# 14_PHY_FE_41-48.net
KiCad netlist of a schematic drawn in Altium Designer
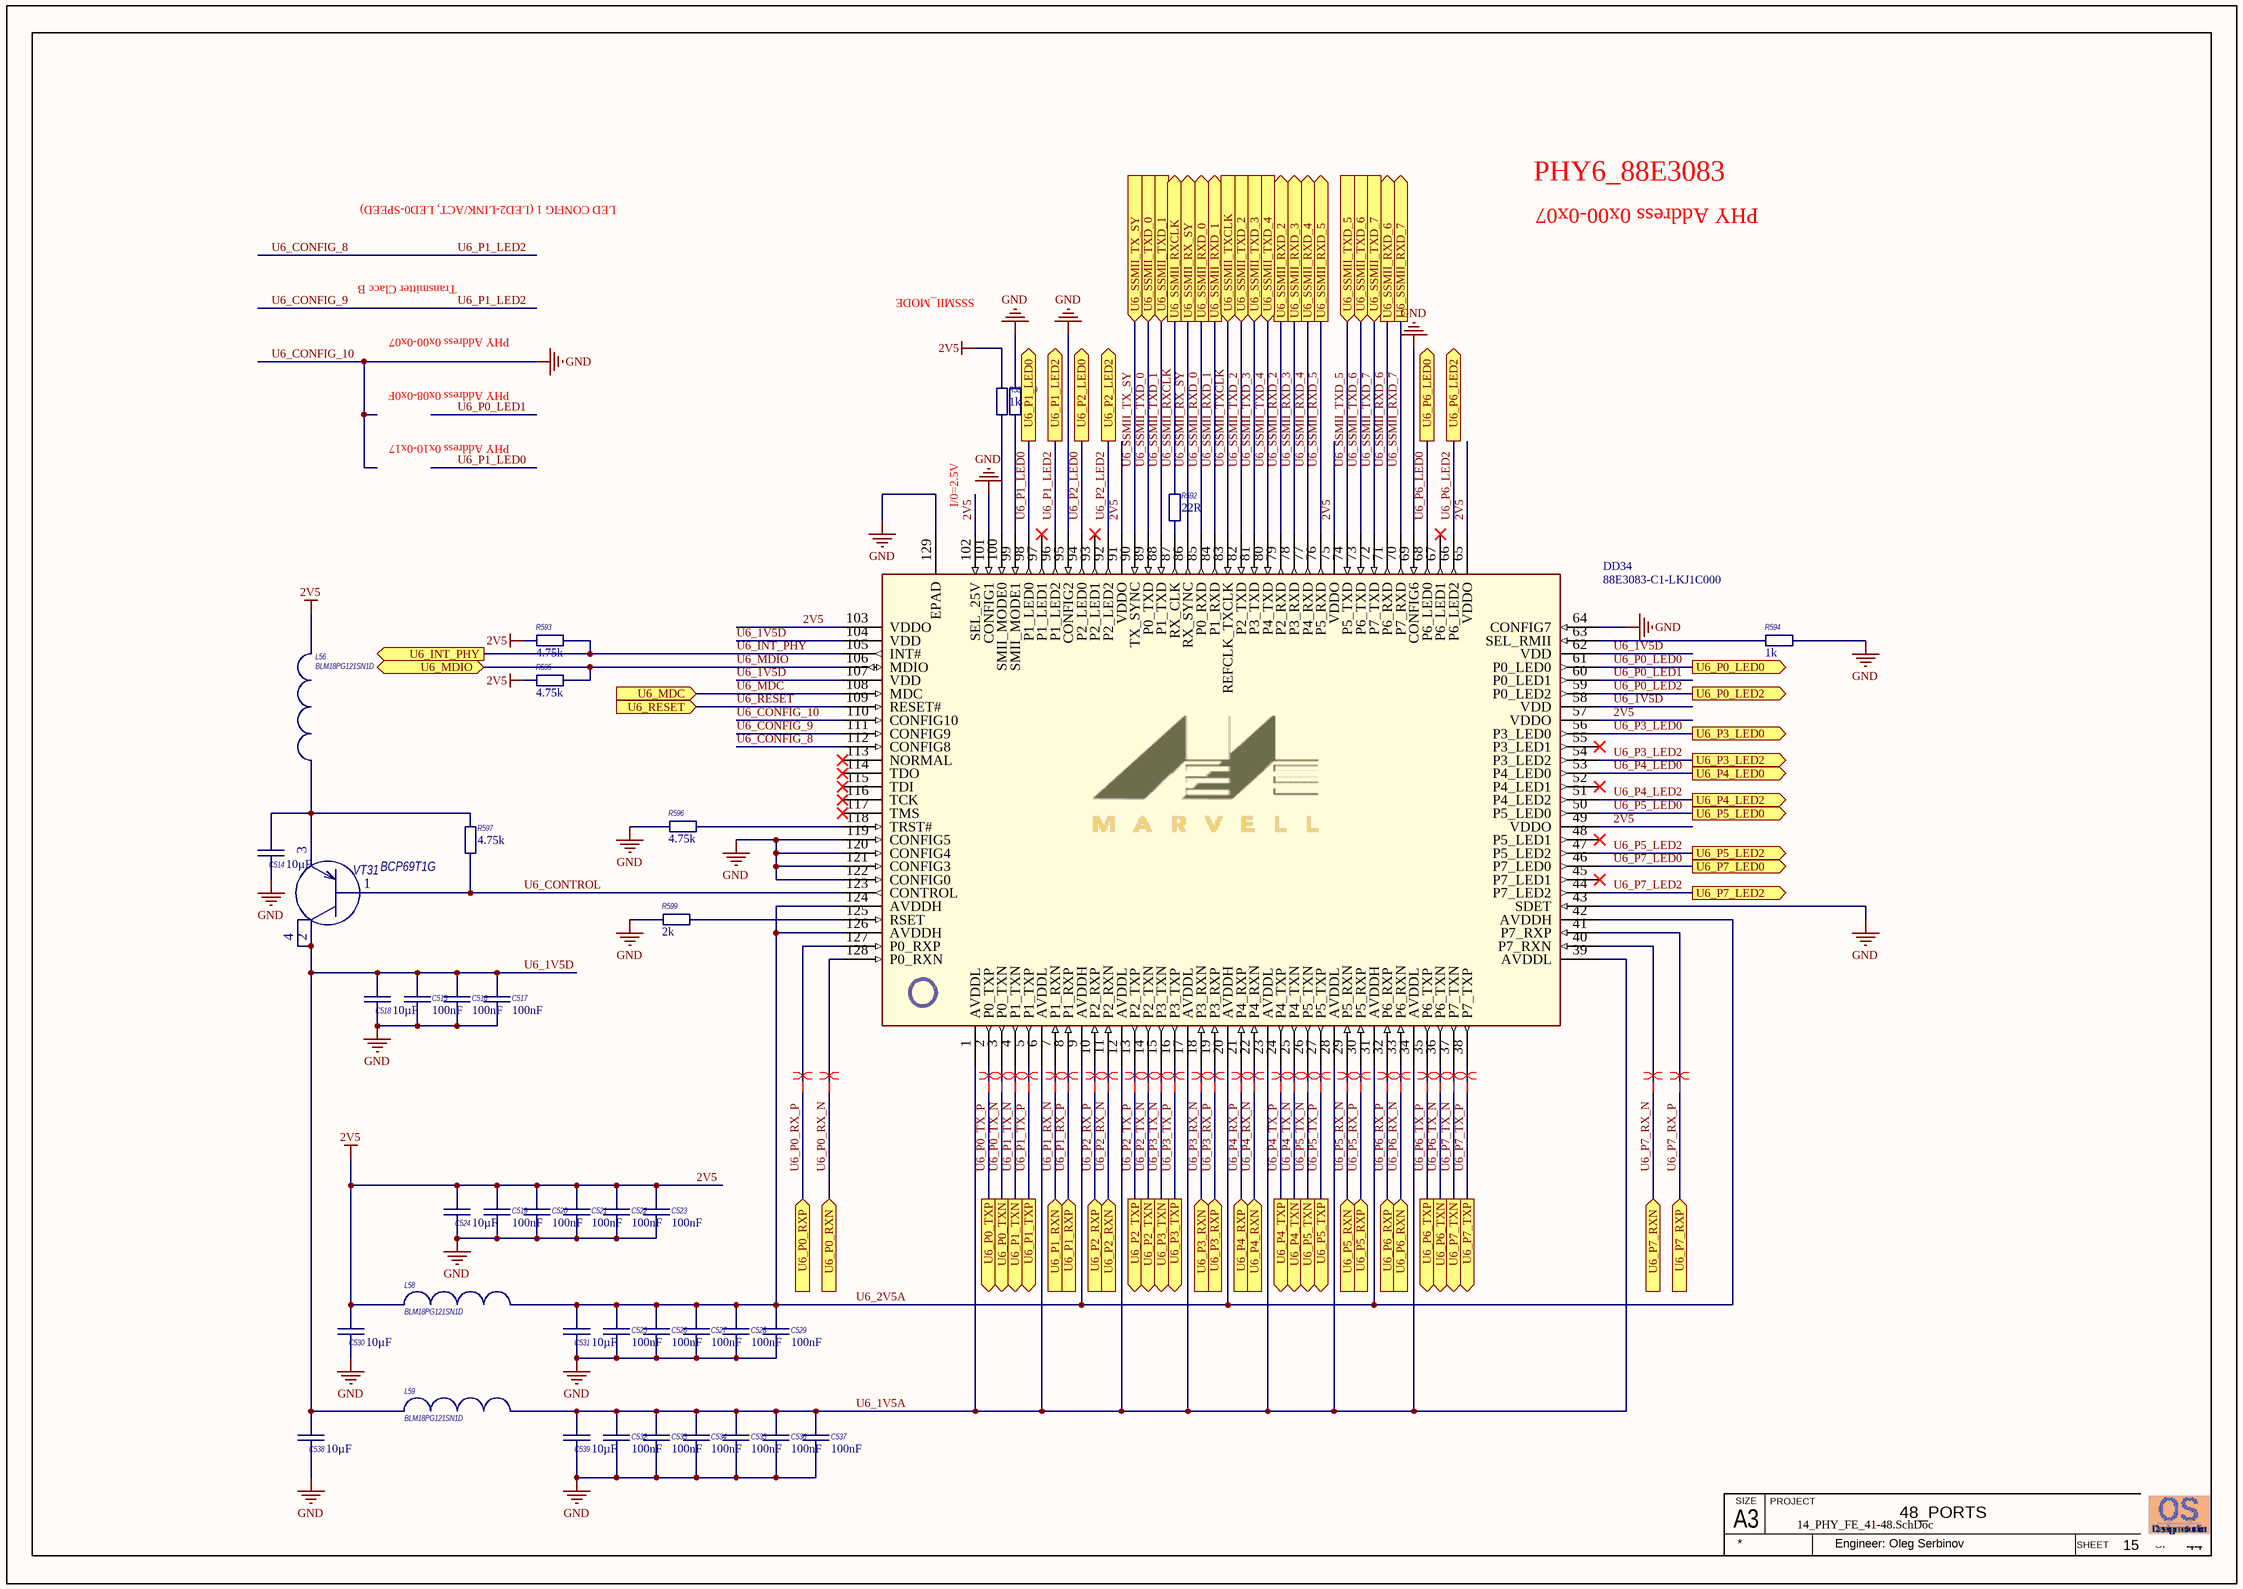
[diagram p0: 14_PHY_FE_41-48.SchDoc]

(export (version "E")
  (design (tool "Eeschema 10.0.6"))
  (components
    (comp (ref "C514")
      (value "GRM21BR61C106KE15")
      (footprint "CAPC2012[0805]")
      (description "C0805, 10uF 10%, 16V, X5R")
      (fields
        (field (name "MANUFACTURER") "Murata")
        (field (name "TOLERANCE") "±10%")
        (field (name "CAPACITANCE") "10µF")
      )
      (libsource (lib "CAPACITORS") (part "GRM21BR61C106KE15"))
    )
    (comp (ref "C515")
      (value "GRM155R71E104KE14D")
      (footprint "C0402_IPC High Density")
      (description "C0402, 100nF, 25V, X7R")
      (fields
        (field (name "MANUFACTURER") "Murata")
        (field (name "CAPACITANCE") "100nF")
        (field (name "CUSTOMER PART NUMBER") "Конденсатор, 100n, 0402, 25V, X7R, 10%")
      )
      (libsource (lib "CAPACITORS") (part "GRM155R71E104KE14D"))
    )
    (comp (ref "C516")
      (value "GRM155R71E104KE14D")
      (footprint "C0402_IPC High Density")
      (description "C0402, 100nF, 25V, X7R")
      (fields
        (field (name "MANUFACTURER") "Murata")
        (field (name "CAPACITANCE") "100nF")
        (field (name "CUSTOMER PART NUMBER") "Конденсатор, 100n, 0402, 25V, X7R, 10%")
      )
      (libsource (lib "CAPACITORS") (part "GRM155R71E104KE14D"))
    )
    (comp (ref "C517")
      (value "GRM155R71E104KE14D")
      (footprint "C0402_IPC High Density")
      (description "C0402, 100nF, 25V, X7R")
      (fields
        (field (name "MANUFACTURER") "Murata")
        (field (name "CAPACITANCE") "100nF")
        (field (name "CUSTOMER PART NUMBER") "Конденсатор, 100n, 0402, 25V, X7R, 10%")
      )
      (libsource (lib "CAPACITORS") (part "GRM155R71E104KE14D"))
    )
    (comp (ref "C518")
      (value "GRM21BR61C106KE15")
      (footprint "CAPC2012[0805]")
      (description "C0805, 10uF 10%, 16V, X5R")
      (fields
        (field (name "MANUFACTURER") "Murata")
        (field (name "TOLERANCE") "±10%")
        (field (name "CAPACITANCE") "10µF")
      )
      (libsource (lib "CAPACITORS") (part "GRM21BR61C106KE15"))
    )
    (comp (ref "C519")
      (value "GRM155R71E104KE14D")
      (footprint "C0402_IPC High Density")
      (description "C0402, 100nF, 25V, X7R")
      (fields
        (field (name "MANUFACTURER") "Murata")
        (field (name "CAPACITANCE") "100nF")
        (field (name "CUSTOMER PART NUMBER") "Конденсатор, 100n, 0402, 25V, X7R, 10%")
      )
      (libsource (lib "CAPACITORS") (part "GRM155R71E104KE14D"))
    )
    (comp (ref "C520")
      (value "GRM155R71E104KE14D")
      (footprint "C0402_IPC High Density")
      (description "C0402, 100nF, 25V, X7R")
      (fields
        (field (name "MANUFACTURER") "Murata")
        (field (name "CAPACITANCE") "100nF")
        (field (name "CUSTOMER PART NUMBER") "Конденсатор, 100n, 0402, 25V, X7R, 10%")
      )
      (libsource (lib "CAPACITORS") (part "GRM155R71E104KE14D"))
    )
    (comp (ref "C521")
      (value "GRM155R71E104KE14D")
      (footprint "C0402_IPC High Density")
      (description "C0402, 100nF, 25V, X7R")
      (fields
        (field (name "MANUFACTURER") "Murata")
        (field (name "CAPACITANCE") "100nF")
        (field (name "CUSTOMER PART NUMBER") "Конденсатор, 100n, 0402, 25V, X7R, 10%")
      )
      (libsource (lib "CAPACITORS") (part "GRM155R71E104KE14D"))
    )
    (comp (ref "C522")
      (value "GRM155R71E104KE14D")
      (footprint "C0402_IPC High Density")
      (description "C0402, 100nF, 25V, X7R")
      (fields
        (field (name "MANUFACTURER") "Murata")
        (field (name "CAPACITANCE") "100nF")
        (field (name "CUSTOMER PART NUMBER") "Конденсатор, 100n, 0402, 25V, X7R, 10%")
      )
      (libsource (lib "CAPACITORS") (part "GRM155R71E104KE14D"))
    )
    (comp (ref "C523")
      (value "GRM155R71E104KE14D")
      (footprint "C0402_IPC High Density")
      (description "C0402, 100nF, 25V, X7R")
      (fields
        (field (name "MANUFACTURER") "Murata")
        (field (name "CAPACITANCE") "100nF")
        (field (name "CUSTOMER PART NUMBER") "Конденсатор, 100n, 0402, 25V, X7R, 10%")
      )
      (libsource (lib "CAPACITORS") (part "GRM155R71E104KE14D"))
    )
    (comp (ref "C524")
      (value "GRM21BR61C106KE15")
      (footprint "CAPC2012[0805]")
      (description "C0805, 10uF 10%, 16V, X5R")
      (fields
        (field (name "MANUFACTURER") "Murata")
        (field (name "TOLERANCE") "±10%")
        (field (name "CAPACITANCE") "10µF")
      )
      (libsource (lib "CAPACITORS") (part "GRM21BR61C106KE15"))
    )
    (comp (ref "C525")
      (value "GRM155R71E104KE14D")
      (footprint "C0402_IPC High Density")
      (description "C0402, 100nF, 25V, X7R")
      (fields
        (field (name "MANUFACTURER") "Murata")
        (field (name "CAPACITANCE") "100nF")
        (field (name "CUSTOMER PART NUMBER") "Конденсатор, 100n, 0402, 25V, X7R, 10%")
      )
      (libsource (lib "CAPACITORS") (part "GRM155R71E104KE14D"))
    )
    (comp (ref "C526")
      (value "GRM155R71E104KE14D")
      (footprint "C0402_IPC High Density")
      (description "C0402, 100nF, 25V, X7R")
      (fields
        (field (name "MANUFACTURER") "Murata")
        (field (name "CAPACITANCE") "100nF")
        (field (name "CUSTOMER PART NUMBER") "Конденсатор, 100n, 0402, 25V, X7R, 10%")
      )
      (libsource (lib "CAPACITORS") (part "GRM155R71E104KE14D"))
    )
    (comp (ref "C527")
      (value "GRM155R71E104KE14D")
      (footprint "C0402_IPC High Density")
      (description "C0402, 100nF, 25V, X7R")
      (fields
        (field (name "MANUFACTURER") "Murata")
        (field (name "CAPACITANCE") "100nF")
        (field (name "CUSTOMER PART NUMBER") "Конденсатор, 100n, 0402, 25V, X7R, 10%")
      )
      (libsource (lib "CAPACITORS") (part "GRM155R71E104KE14D"))
    )
    (comp (ref "C528")
      (value "GRM155R71E104KE14D")
      (footprint "C0402_IPC High Density")
      (description "C0402, 100nF, 25V, X7R")
      (fields
        (field (name "MANUFACTURER") "Murata")
        (field (name "CAPACITANCE") "100nF")
        (field (name "CUSTOMER PART NUMBER") "Конденсатор, 100n, 0402, 25V, X7R, 10%")
      )
      (libsource (lib "CAPACITORS") (part "GRM155R71E104KE14D"))
    )
    (comp (ref "C529")
      (value "GRM155R71E104KE14D")
      (footprint "C0402_IPC High Density")
      (description "C0402, 100nF, 25V, X7R")
      (fields
        (field (name "MANUFACTURER") "Murata")
        (field (name "CAPACITANCE") "100nF")
        (field (name "CUSTOMER PART NUMBER") "Конденсатор, 100n, 0402, 25V, X7R, 10%")
      )
      (libsource (lib "CAPACITORS") (part "GRM155R71E104KE14D"))
    )
    (comp (ref "C530")
      (value "GRM21BR61C106KE15")
      (footprint "CAPC2012[0805]")
      (description "C0805, 10uF 10%, 16V, X5R")
      (fields
        (field (name "MANUFACTURER") "Murata")
        (field (name "TOLERANCE") "±10%")
        (field (name "CAPACITANCE") "10µF")
      )
      (libsource (lib "CAPACITORS") (part "GRM21BR61C106KE15"))
    )
    (comp (ref "C531")
      (value "GRM21BR61C106KE15")
      (footprint "CAPC2012[0805]")
      (description "C0805, 10uF 10%, 16V, X5R")
      (fields
        (field (name "MANUFACTURER") "Murata")
        (field (name "TOLERANCE") "±10%")
        (field (name "CAPACITANCE") "10µF")
      )
      (libsource (lib "CAPACITORS") (part "GRM21BR61C106KE15"))
    )
    (comp (ref "C532")
      (value "GRM155R71E104KE14D")
      (footprint "C0402_IPC High Density")
      (description "C0402, 100nF, 25V, X7R")
      (fields
        (field (name "MANUFACTURER") "Murata")
        (field (name "CAPACITANCE") "100nF")
        (field (name "CUSTOMER PART NUMBER") "Конденсатор, 100n, 0402, 25V, X7R, 10%")
      )
      (libsource (lib "CAPACITORS") (part "GRM155R71E104KE14D"))
    )
    (comp (ref "C533")
      (value "GRM155R71E104KE14D")
      (footprint "C0402_IPC High Density")
      (description "C0402, 100nF, 25V, X7R")
      (fields
        (field (name "MANUFACTURER") "Murata")
        (field (name "CAPACITANCE") "100nF")
        (field (name "CUSTOMER PART NUMBER") "Конденсатор, 100n, 0402, 25V, X7R, 10%")
      )
      (libsource (lib "CAPACITORS") (part "GRM155R71E104KE14D"))
    )
    (comp (ref "C534")
      (value "GRM155R71E104KE14D")
      (footprint "C0402_IPC High Density")
      (description "C0402, 100nF, 25V, X7R")
      (fields
        (field (name "MANUFACTURER") "Murata")
        (field (name "CAPACITANCE") "100nF")
        (field (name "CUSTOMER PART NUMBER") "Конденсатор, 100n, 0402, 25V, X7R, 10%")
      )
      (libsource (lib "CAPACITORS") (part "GRM155R71E104KE14D"))
    )
    (comp (ref "C535")
      (value "GRM155R71E104KE14D")
      (footprint "C0402_IPC High Density")
      (description "C0402, 100nF, 25V, X7R")
      (fields
        (field (name "MANUFACTURER") "Murata")
        (field (name "CAPACITANCE") "100nF")
        (field (name "CUSTOMER PART NUMBER") "Конденсатор, 100n, 0402, 25V, X7R, 10%")
      )
      (libsource (lib "CAPACITORS") (part "GRM155R71E104KE14D"))
    )
    (comp (ref "C536")
      (value "GRM155R71E104KE14D")
      (footprint "C0402_IPC High Density")
      (description "C0402, 100nF, 25V, X7R")
      (fields
        (field (name "MANUFACTURER") "Murata")
        (field (name "CAPACITANCE") "100nF")
        (field (name "CUSTOMER PART NUMBER") "Конденсатор, 100n, 0402, 25V, X7R, 10%")
      )
      (libsource (lib "CAPACITORS") (part "GRM155R71E104KE14D"))
    )
    (comp (ref "C537")
      (value "GRM155R71E104KE14D")
      (footprint "C0402_IPC High Density")
      (description "C0402, 100nF, 25V, X7R")
      (fields
        (field (name "MANUFACTURER") "Murata")
        (field (name "CAPACITANCE") "100nF")
        (field (name "CUSTOMER PART NUMBER") "Конденсатор, 100n, 0402, 25V, X7R, 10%")
      )
      (libsource (lib "CAPACITORS") (part "GRM155R71E104KE14D"))
    )
    (comp (ref "C538")
      (value "GRM21BR61C106KE15")
      (footprint "CAPC2012[0805]")
      (description "C0805, 10uF 10%, 16V, X5R")
      (fields
        (field (name "MANUFACTURER") "Murata")
        (field (name "TOLERANCE") "±10%")
        (field (name "CAPACITANCE") "10µF")
      )
      (libsource (lib "CAPACITORS") (part "GRM21BR61C106KE15"))
    )
    (comp (ref "C539")
      (value "GRM21BR61C106KE15")
      (footprint "CAPC2012[0805]")
      (description "C0805, 10uF 10%, 16V, X5R")
      (fields
        (field (name "MANUFACTURER") "Murata")
        (field (name "TOLERANCE") "±10%")
        (field (name "CAPACITANCE") "10µF")
      )
      (libsource (lib "CAPACITORS") (part "GRM21BR61C106KE15"))
    )
    (comp (ref "DD34")
      (value "88E3083-C1-LKJ1C000")
      (footprint "LQFP-128N")
      (description "IC 10/100BASE-T OCTAL PHY")
      (fields
        (field (name "CUSTOMER PART NUMBER") "Микросхема, 88E3083-C1-LKJ1C000, IC 10/100BASE-T OCTAL PHY, 128 LQFP")
        (field (name "MANUFACTURER") "Marvell Technology Group")
      )
      (libsource (lib "DIGITAL and ANALIG ICs") (part "88E3083-C1-LKJ1C000"))
    )
    (comp (ref "L56")
      (value "BLM18PG121SN1D")
      (footprint "INDC1608X95N")
      (description "FILTER BLM18 (0603, 2A)")
      (fields
        (field (name "MANUFACTURER") "Murata")
        (field (name "RPART NUMBER") "MPZ1608S121ATAH0 ; CIC10P121NC ; MPZ1608S121ATDH5 ; BLM18PG121SH1D ; 742792625")
      )
      (libsource (lib "INDUCTORS") (part "BLM18PG121SN1D"))
    )
    (comp (ref "L58")
      (value "BLM18PG121SN1D")
      (footprint "INDC1608X95N")
      (description "FILTER BLM18 (0603, 2A)")
      (fields
        (field (name "MANUFACTURER") "Murata")
        (field (name "RPART NUMBER") "MPZ1608S121ATAH0 ; CIC10P121NC ; MPZ1608S121ATDH5 ; BLM18PG121SH1D ; 742792625")
      )
      (libsource (lib "INDUCTORS") (part "BLM18PG121SN1D"))
    )
    (comp (ref "L59")
      (value "BLM18PG121SN1D")
      (footprint "INDC1608X95N")
      (description "FILTER BLM18 (0603, 2A)")
      (fields
        (field (name "MANUFACTURER") "Murata")
        (field (name "RPART NUMBER") "MPZ1608S121ATAH0 ; CIC10P121NC ; MPZ1608S121ATDH5 ; BLM18PG121SH1D ; 742792625")
      )
      (libsource (lib "INDUCTORS") (part "BLM18PG121SN1D"))
    )
    (comp (ref "R588")
      (value "ERJ-2RKF1001X")
      (footprint "R0402_IPC High Density")
      (description "R0402, 1k 1%")
      (fields
        (field (name "MANUFACTURER") "Panasonic")
        (field (name "TOLERANCE") "1 %")
        (field (name "RESISTANCE") "1k")
      )
      (libsource (lib "RESISTOR") (part "ERJ-2RKF1001X"))
    )
    (comp (ref "R589")
      (value "ERJ-2RKF1001X")
      (footprint "R0402_IPC High Density")
      (description "R0402, 1k 1%")
      (fields
        (field (name "MANUFACTURER") "Panasonic")
        (field (name "TOLERANCE") "1 %")
        (field (name "RESISTANCE") "1k")
      )
      (libsource (lib "RESISTOR") (part "ERJ-2RKF1001X"))
    )
    (comp (ref "R592")
      (value "ERJ-2RKF22R0X")
      (footprint "R0402_IPC High Density")
      (description "R0402, 22R 1%")
      (fields
        (field (name "MANUFACTURER") "Panasonic")
        (field (name "RESISTANCE") "22R")
        (field (name "CUSTOMER PART NUMBER") "Резистор, 22R, 0402, 1%")
      )
      (libsource (lib "RESISTOR") (part "ERJ-2RKF22R0X"))
    )
    (comp (ref "R593")
      (value "ERJ-2RKF4751X")
      (footprint "R0402_IPC High Density")
      (description "R0402, 4.75k 1%")
      (fields
        (field (name "TOLERANCE") "±1%")
        (field (name "MANUFACTURER") "Panasonic")
        (field (name "RESISTANCE (OHMS)") "4.75k")
      )
      (libsource (lib "RESISTOR") (part "ERJ-2RKF4751X"))
    )
    (comp (ref "R594")
      (value "ERJ-2RKF1001X")
      (footprint "R0402_IPC High Density")
      (description "R0402, 1k 1%")
      (fields
        (field (name "MANUFACTURER") "Panasonic")
        (field (name "TOLERANCE") "1 %")
        (field (name "RESISTANCE") "1k")
      )
      (libsource (lib "RESISTOR") (part "ERJ-2RKF1001X"))
    )
    (comp (ref "R595")
      (value "ERJ-2RKF4751X")
      (footprint "R0402_IPC High Density")
      (description "R0402, 4.75k 1%")
      (fields
        (field (name "TOLERANCE") "±1%")
        (field (name "MANUFACTURER") "Panasonic")
        (field (name "RESISTANCE (OHMS)") "4.75k")
      )
      (libsource (lib "RESISTOR") (part "ERJ-2RKF4751X"))
    )
    (comp (ref "R596")
      (value "ERJ-2RKF4751X")
      (footprint "R0402_IPC High Density")
      (description "R0402, 4.75k 1%")
      (fields
        (field (name "TOLERANCE") "±1%")
        (field (name "MANUFACTURER") "Panasonic")
        (field (name "RESISTANCE (OHMS)") "4.75k")
      )
      (libsource (lib "RESISTOR") (part "ERJ-2RKF4751X"))
    )
    (comp (ref "R597")
      (value "ERJ-2RKF4751X")
      (footprint "R0402_IPC High Density")
      (description "R0402, 4.75k 1%")
      (fields
        (field (name "TOLERANCE") "±1%")
        (field (name "MANUFACTURER") "Panasonic")
        (field (name "RESISTANCE (OHMS)") "4.75k")
      )
      (libsource (lib "RESISTOR") (part "ERJ-2RKF4751X"))
    )
    (comp (ref "R599")
      (value "ERJ-2RKF2001X")
      (footprint "R0402_IPC High Density")
      (description "R0402, 2k 1%")
      (fields
        (field (name "TOLERANCE") "±1%")
        (field (name "MANUFACTURER") "Panasonic")
        (field (name "RESISTANCE (OHMS)") "2k")
      )
      (libsource (lib "RESISTOR") (part "ERJ-2RKF2001X"))
    )
    (comp (ref "VT31")
      (value "BCP69T1G")
      (footprint "SOT223_N")
      (description "TRANSISTOR PNP -20V -1A SOT-223")
      (fields
        (field (name "MANUFACTURER") "ON Semiconductor")
        (field (name "MANUFACTURER PART NUMBER") "BCP69T1")
      )
      (libsource (lib "TRANSISTORS") (part "BCP69T1"))
    )
  )
  (nets
    (net (code "1") (name "/U6_1V5A") (class "Default")
      (node (ref "C532") (pin "2") (pintype "passive"))
      (node (ref "C533") (pin "2") (pintype "passive"))
      (node (ref "C534") (pin "2") (pintype "passive"))
      (node (ref "C535") (pin "2") (pintype "passive"))
      (node (ref "C536") (pin "2") (pintype "passive"))
      (node (ref "C537") (pin "2") (pintype "passive"))
      (node (ref "C539") (pin "2") (pintype "passive"))
      (node (ref "DD34") (pin "1") (pinfunction "AVDDL_1") (pintype "power_in"))
      (node (ref "DD34") (pin "12") (pinfunction "AVDDL_12") (pintype "power_in"))
      (node (ref "DD34") (pin "17") (pinfunction "AVDDL_17") (pintype "power_in"))
      (node (ref "DD34") (pin "23") (pinfunction "AVDDL_23") (pintype "power_in"))
      (node (ref "DD34") (pin "28") (pinfunction "AVDDL_28") (pintype "power_in"))
      (node (ref "DD34") (pin "34") (pinfunction "AVDDL_34") (pintype "power_in"))
      (node (ref "DD34") (pin "39") (pinfunction "AVDDL_39") (pintype "power_in"))
      (node (ref "DD34") (pin "6") (pinfunction "AVDDL_6") (pintype "power_in"))
      (node (ref "L59") (pin "2") (pinfunction "2_2") (pintype "passive"))
    )
    (net (code "2") (name "/U6_1V5D") (class "Default")
      (node (ref "C515") (pin "2") (pintype "passive"))
      (node (ref "C516") (pin "2") (pintype "passive"))
      (node (ref "C517") (pin "2") (pintype "passive"))
      (node (ref "C518") (pin "2") (pintype "passive"))
      (node (ref "C538") (pin "2") (pintype "passive"))
      (node (ref "DD34") (pin "104") (pinfunction "VDD_104") (pintype "power_in"))
      (node (ref "DD34") (pin "107") (pinfunction "VDD_107") (pintype "power_in"))
      (node (ref "DD34") (pin "58") (pinfunction "VDD_58") (pintype "power_in"))
      (node (ref "DD34") (pin "62") (pinfunction "VDD_62") (pintype "power_in"))
      (node (ref "L59") (pin "1") (pinfunction "1_1") (pintype "passive"))
      (node (ref "VT31") (pin "2") (pinfunction "K_2") (pintype "passive"))
      (node (ref "VT31") (pin "4") (pinfunction "K_4") (pintype "passive"))
    )
    (net (code "3") (name "/U6_2V5A") (class "Default")
      (node (ref "C525") (pin "2") (pintype "passive"))
      (node (ref "C526") (pin "2") (pintype "passive"))
      (node (ref "C527") (pin "2") (pintype "passive"))
      (node (ref "C528") (pin "2") (pintype "passive"))
      (node (ref "C529") (pin "2") (pintype "passive"))
      (node (ref "C531") (pin "2") (pintype "passive"))
      (node (ref "DD34") (pin "124") (pinfunction "AVDDH_124") (pintype "power_in"))
      (node (ref "DD34") (pin "126") (pinfunction "AVDDH_126") (pintype "power_in"))
      (node (ref "DD34") (pin "20") (pinfunction "AVDDH_20") (pintype "power_in"))
      (node (ref "DD34") (pin "31") (pinfunction "AVDDH_31") (pintype "power_in"))
      (node (ref "DD34") (pin "42") (pinfunction "AVDDH_42") (pintype "power_in"))
      (node (ref "DD34") (pin "9") (pinfunction "AVDDH_9") (pintype "power_in"))
      (node (ref "L58") (pin "2") (pinfunction "2_2") (pintype "passive"))
    )
    (net (code "4") (name "/U6_CONFIG_8") (class "Default")
      (node (ref "DD34") (pin "111") (pinfunction "CONFIG9_111") (pintype "input"))
      (node (ref "DD34") (pin "112") (pinfunction "CONFIG8_112") (pintype "input"))
      (node (ref "DD34") (pin "96") (pinfunction "P1_LED2_96") (pintype "output"))
    )
    (net (code "5") (name "/U6_CONTROL") (class "Default")
      (node (ref "DD34") (pin "123") (pinfunction "CONTROL_123") (pintype "output"))
      (node (ref "R597") (pin "1") (pintype "passive"))
      (node (ref "VT31") (pin "1") (pinfunction "B_1") (pintype "passive"))
    )
    (net (code "6") (name "/U6_INT_PHY") (class "Default")
      (node (ref "DD34") (pin "105") (pinfunction "INT#_105") (pintype "output"))
      (node (ref "R593") (pin "2") (pintype "passive"))
    )
    (net (code "7") (name "/U6_MDC") (class "Default")
      (node (ref "DD34") (pin "108") (pinfunction "MDC_108") (pintype "input"))
    )
    (net (code "8") (name "/U6_MDIO") (class "Default")
      (node (ref "DD34") (pin "106") (pinfunction "MDIO_106") (pintype "bidirectional"))
      (node (ref "R595") (pin "2") (pintype "passive"))
    )
    (net (code "9") (name "/U6_P0_LED0") (class "Default")
      (node (ref "DD34") (pin "61") (pinfunction "P0_LED0_61") (pintype "output"))
    )
    (net (code "10") (name "/U6_P0_LED1") (class "Default")
      (node (ref "DD34") (pin "60") (pinfunction "P0_LED1_60") (pintype "output"))
    )
    (net (code "11") (name "/U6_P0_LED2") (class "Default")
      (node (ref "DD34") (pin "59") (pinfunction "P0_LED2_59") (pintype "output"))
    )
    (net (code "12") (name "/U6_P0_RX_N") (class "Default")
      (node (ref "DD34") (pin "128") (pinfunction "P0_RXN_128") (pintype "input"))
    )
    (net (code "13") (name "/U6_P0_RX_P") (class "Default")
      (node (ref "DD34") (pin "127") (pinfunction "P0_RXP_127") (pintype "input"))
    )
    (net (code "14") (name "/U6_P0_TX_N") (class "Default")
      (node (ref "DD34") (pin "3") (pinfunction "P0_TXN_3") (pintype "output"))
    )
    (net (code "15") (name "/U6_P0_TX_P") (class "Default")
      (node (ref "DD34") (pin "2") (pinfunction "P0_TXP_2") (pintype "output"))
    )
    (net (code "16") (name "/U6_P1_LED0") (class "Default")
      (node (ref "DD34") (pin "98") (pinfunction "P1_LED0_98") (pintype "output"))
    )
    (net (code "17") (name "/U6_P1_RX_N") (class "Default")
      (node (ref "DD34") (pin "7") (pinfunction "P1_RXN_7") (pintype "input"))
    )
    (net (code "18") (name "/U6_P1_RX_P") (class "Default")
      (node (ref "DD34") (pin "8") (pinfunction "P1_RXP_8") (pintype "input"))
    )
    (net (code "19") (name "/U6_P1_TX_N") (class "Default")
      (node (ref "DD34") (pin "4") (pinfunction "P1_TXN_4") (pintype "output"))
    )
    (net (code "20") (name "/U6_P1_TX_P") (class "Default")
      (node (ref "DD34") (pin "5") (pinfunction "P1_TXP_5") (pintype "output"))
    )
    (net (code "21") (name "/U6_P2_LED0") (class "Default")
      (node (ref "DD34") (pin "94") (pinfunction "P2_LED0_94") (pintype "output"))
    )
    (net (code "22") (name "/U6_P2_LED2") (class "Default")
      (node (ref "DD34") (pin "92") (pinfunction "P2_LED2_92") (pintype "output"))
    )
    (net (code "23") (name "/U6_P2_RX_N") (class "Default")
      (node (ref "DD34") (pin "11") (pinfunction "P2_RXN_11") (pintype "input"))
    )
    (net (code "24") (name "/U6_P2_RX_P") (class "Default")
      (node (ref "DD34") (pin "10") (pinfunction "P2_RXP_10") (pintype "input"))
    )
    (net (code "25") (name "/U6_P2_TX_N") (class "Default")
      (node (ref "DD34") (pin "14") (pinfunction "P2_TXN_14") (pintype "output"))
    )
    (net (code "26") (name "/U6_P2_TX_P") (class "Default")
      (node (ref "DD34") (pin "13") (pinfunction "P2_TXP_13") (pintype "output"))
    )
    (net (code "27") (name "/U6_P3_LED0") (class "Default")
      (node (ref "DD34") (pin "56") (pinfunction "P3_LED0_56") (pintype "output"))
    )
    (net (code "28") (name "/U6_P3_LED2") (class "Default")
      (node (ref "DD34") (pin "54") (pinfunction "P3_LED2_54") (pintype "output"))
    )
    (net (code "29") (name "/U6_P3_RX_N") (class "Default")
      (node (ref "DD34") (pin "18") (pinfunction "P3_RXN_18") (pintype "input"))
    )
    (net (code "30") (name "/U6_P3_RX_P") (class "Default")
      (node (ref "DD34") (pin "19") (pinfunction "P3_RXP_19") (pintype "input"))
    )
    (net (code "31") (name "/U6_P3_TX_N") (class "Default")
      (node (ref "DD34") (pin "15") (pinfunction "P3_TXN_15") (pintype "output"))
    )
    (net (code "32") (name "/U6_P3_TX_P") (class "Default")
      (node (ref "DD34") (pin "16") (pinfunction "P3_TXP_16") (pintype "output"))
    )
    (net (code "33") (name "/U6_P4_LED0") (class "Default")
      (node (ref "DD34") (pin "53") (pinfunction "P4_LED0_53") (pintype "output"))
    )
    (net (code "34") (name "/U6_P4_LED2") (class "Default")
      (node (ref "DD34") (pin "51") (pinfunction "P4_LED2_51") (pintype "output"))
    )
    (net (code "35") (name "/U6_P4_RX_N") (class "Default")
      (node (ref "DD34") (pin "22") (pinfunction "P4_RXN_22") (pintype "input"))
    )
    (net (code "36") (name "/U6_P4_RX_P") (class "Default")
      (node (ref "DD34") (pin "21") (pinfunction "P4_RXP_21") (pintype "input"))
    )
    (net (code "37") (name "/U6_P4_TX_N") (class "Default")
      (node (ref "DD34") (pin "25") (pinfunction "P4_TXN_25") (pintype "output"))
    )
    (net (code "38") (name "/U6_P4_TX_P") (class "Default")
      (node (ref "DD34") (pin "24") (pinfunction "P4_TXP_24") (pintype "output"))
    )
    (net (code "39") (name "/U6_P5_LED0") (class "Default")
      (node (ref "DD34") (pin "50") (pinfunction "P5_LED0_50") (pintype "output"))
    )
    (net (code "40") (name "/U6_P5_LED2") (class "Default")
      (node (ref "DD34") (pin "47") (pinfunction "P5_LED2_47") (pintype "output"))
    )
    (net (code "41") (name "/U6_P5_RX_N") (class "Default")
      (node (ref "DD34") (pin "29") (pinfunction "P5_RXN_29") (pintype "input"))
    )
    (net (code "42") (name "/U6_P5_RX_P") (class "Default")
      (node (ref "DD34") (pin "30") (pinfunction "P5_RXP_30") (pintype "input"))
    )
    (net (code "43") (name "/U6_P5_TX_N") (class "Default")
      (node (ref "DD34") (pin "26") (pinfunction "P5_TXN_26") (pintype "output"))
    )
    (net (code "44") (name "/U6_P5_TX_P") (class "Default")
      (node (ref "DD34") (pin "27") (pinfunction "P5_TXP_27") (pintype "output"))
    )
    (net (code "45") (name "/U6_P6_LED0") (class "Default")
      (node (ref "DD34") (pin "68") (pinfunction "P6_LED0_68") (pintype "output"))
    )
    (net (code "46") (name "/U6_P6_LED2") (class "Default")
      (node (ref "DD34") (pin "66") (pinfunction "P6_LED2_66") (pintype "output"))
    )
    (net (code "47") (name "/U6_P6_RX_N") (class "Default")
      (node (ref "DD34") (pin "33") (pinfunction "P6_RXN_33") (pintype "input"))
    )
    (net (code "48") (name "/U6_P6_RX_P") (class "Default")
      (node (ref "DD34") (pin "32") (pinfunction "P6_RXP_32") (pintype "input"))
    )
    (net (code "49") (name "/U6_P6_TX_N") (class "Default")
      (node (ref "DD34") (pin "36") (pinfunction "P6_TXN_36") (pintype "output"))
    )
    (net (code "50") (name "/U6_P6_TX_P") (class "Default")
      (node (ref "DD34") (pin "35") (pinfunction "P6_TXP_35") (pintype "output"))
    )
    (net (code "51") (name "/U6_P7_LED0") (class "Default")
      (node (ref "DD34") (pin "46") (pinfunction "P7_LED0_46") (pintype "output"))
    )
    (net (code "52") (name "/U6_P7_LED2") (class "Default")
      (node (ref "DD34") (pin "44") (pinfunction "P7_LED2_44") (pintype "output"))
    )
    (net (code "53") (name "/U6_P7_RX_N") (class "Default")
      (node (ref "DD34") (pin "40") (pinfunction "P7_RXN_40") (pintype "input"))
    )
    (net (code "54") (name "/U6_P7_RX_P") (class "Default")
      (node (ref "DD34") (pin "41") (pinfunction "P7_RXP_41") (pintype "input"))
    )
    (net (code "55") (name "/U6_P7_TX_N") (class "Default")
      (node (ref "DD34") (pin "37") (pinfunction "P7_TXN_37") (pintype "output"))
    )
    (net (code "56") (name "/U6_P7_TX_P") (class "Default")
      (node (ref "DD34") (pin "38") (pinfunction "P7_TXP_38") (pintype "output"))
    )
    (net (code "57") (name "/U6_RESET") (class "Default")
      (node (ref "DD34") (pin "109") (pinfunction "RESET#_109") (pintype "input"))
    )
    (net (code "58") (name "/U6_SSMII_RXCLK") (class "Default")
      (node (ref "R592") (pin "2") (pintype "passive"))
    )
    (net (code "59") (name "/U6_SSMII_RXD_0") (class "Default")
      (node (ref "DD34") (pin "85") (pinfunction "P0_RXD_85") (pintype "output"))
    )
    (net (code "60") (name "/U6_SSMII_RXD_1") (class "Default")
      (node (ref "DD34") (pin "84") (pinfunction "P1_RXD_84") (pintype "output"))
    )
    (net (code "61") (name "/U6_SSMII_RXD_2") (class "Default")
      (node (ref "DD34") (pin "79") (pinfunction "P2_RXD_79") (pintype "output"))
    )
    (net (code "62") (name "/U6_SSMII_RXD_3") (class "Default")
      (node (ref "DD34") (pin "78") (pinfunction "P3_RXD_78") (pintype "output"))
    )
    (net (code "63") (name "/U6_SSMII_RXD_4") (class "Default")
      (node (ref "DD34") (pin "77") (pinfunction "P4_RXD_77") (pintype "output"))
    )
    (net (code "64") (name "/U6_SSMII_RXD_5") (class "Default")
      (node (ref "DD34") (pin "76") (pinfunction "P5_RXD_76") (pintype "output"))
    )
    (net (code "65") (name "/U6_SSMII_RXD_6") (class "Default")
      (node (ref "DD34") (pin "71") (pinfunction "P6_RXD_71") (pintype "output"))
    )
    (net (code "66") (name "/U6_SSMII_RXD_7") (class "Default")
      (node (ref "DD34") (pin "70") (pinfunction "P7_RXD_70") (pintype "output"))
    )
    (net (code "67") (name "/U6_SSMII_RX_SY") (class "Default")
      (node (ref "DD34") (pin "86") (pinfunction "RX_SYNC_86") (pintype "output"))
    )
    (net (code "68") (name "/U6_SSMII_TXCLK") (class "Default")
      (node (ref "DD34") (pin "83") (pinfunction "REFCLK_TXCLK_83") (pintype "input"))
    )
    (net (code "69") (name "/U6_SSMII_TXD_0") (class "Default")
      (node (ref "DD34") (pin "89") (pinfunction "P0_TXD_89") (pintype "input"))
    )
    (net (code "70") (name "/U6_SSMII_TXD_1") (class "Default")
      (node (ref "DD34") (pin "88") (pinfunction "P1_TXD_88") (pintype "input"))
    )
    (net (code "71") (name "/U6_SSMII_TXD_2") (class "Default")
      (node (ref "DD34") (pin "82") (pinfunction "P2_TXD_82") (pintype "input"))
    )
    (net (code "72") (name "/U6_SSMII_TXD_3") (class "Default")
      (node (ref "DD34") (pin "81") (pinfunction "P3_TXD_81") (pintype "input"))
    )
    (net (code "73") (name "/U6_SSMII_TXD_4") (class "Default")
      (node (ref "DD34") (pin "80") (pinfunction "P4_TXD_80") (pintype "input"))
    )
    (net (code "74") (name "/U6_SSMII_TXD_5") (class "Default")
      (node (ref "DD34") (pin "74") (pinfunction "P5_TXD_74") (pintype "input"))
    )
    (net (code "75") (name "/U6_SSMII_TXD_6") (class "Default")
      (node (ref "DD34") (pin "73") (pinfunction "P6_TXD_73") (pintype "input"))
    )
    (net (code "76") (name "/U6_SSMII_TXD_7") (class "Default")
      (node (ref "DD34") (pin "72") (pinfunction "P7_TXD_72") (pintype "input"))
    )
    (net (code "77") (name "/U6_SSMII_TX_SY") (class "Default")
      (node (ref "DD34") (pin "90") (pinfunction "TX_SYNC_90") (pintype "input"))
    )
    (net (code "78") (name "2V5") (class "Default")
      (node (ref "C519") (pin "2") (pintype "passive"))
      (node (ref "C520") (pin "2") (pintype "passive"))
      (node (ref "C521") (pin "2") (pintype "passive"))
      (node (ref "C522") (pin "2") (pintype "passive"))
      (node (ref "C523") (pin "2") (pintype "passive"))
      (node (ref "C524") (pin "2") (pintype "passive"))
      (node (ref "C530") (pin "2") (pintype "passive"))
      (node (ref "DD34") (pin "102") (pinfunction "SEL_25V_102") (pintype "input"))
      (node (ref "DD34") (pin "103") (pinfunction "VDDO_103") (pintype "power_in"))
      (node (ref "DD34") (pin "49") (pinfunction "VDDO_49") (pintype "power_in"))
      (node (ref "DD34") (pin "57") (pinfunction "VDDO_57") (pintype "power_in"))
      (node (ref "DD34") (pin "65") (pinfunction "VDDO_65") (pintype "power_in"))
      (node (ref "DD34") (pin "75") (pinfunction "VDDO_75") (pintype "power_in"))
      (node (ref "DD34") (pin "91") (pinfunction "VDDO_91") (pintype "power_in"))
      (node (ref "L56") (pin "2") (pinfunction "2_2") (pintype "passive"))
      (node (ref "L58") (pin "1") (pinfunction "1_1") (pintype "passive"))
      (node (ref "R588") (pin "2") (pintype "passive"))
      (node (ref "R593") (pin "1") (pintype "passive"))
      (node (ref "R595") (pin "1") (pintype "passive"))
    )
    (net (code "79") (name "GND") (class "Default")
      (node (ref "C514") (pin "1") (pintype "passive"))
      (node (ref "C515") (pin "1") (pintype "passive"))
      (node (ref "C516") (pin "1") (pintype "passive"))
      (node (ref "C517") (pin "1") (pintype "passive"))
      (node (ref "C518") (pin "1") (pintype "passive"))
      (node (ref "C519") (pin "1") (pintype "passive"))
      (node (ref "C520") (pin "1") (pintype "passive"))
      (node (ref "C521") (pin "1") (pintype "passive"))
      (node (ref "C522") (pin "1") (pintype "passive"))
      (node (ref "C523") (pin "1") (pintype "passive"))
      (node (ref "C524") (pin "1") (pintype "passive"))
      (node (ref "C525") (pin "1") (pintype "passive"))
      (node (ref "C526") (pin "1") (pintype "passive"))
      (node (ref "C527") (pin "1") (pintype "passive"))
      (node (ref "C528") (pin "1") (pintype "passive"))
      (node (ref "C529") (pin "1") (pintype "passive"))
      (node (ref "C530") (pin "1") (pintype "passive"))
      (node (ref "C531") (pin "1") (pintype "passive"))
      (node (ref "C532") (pin "1") (pintype "passive"))
      (node (ref "C533") (pin "1") (pintype "passive"))
      (node (ref "C534") (pin "1") (pintype "passive"))
      (node (ref "C535") (pin "1") (pintype "passive"))
      (node (ref "C536") (pin "1") (pintype "passive"))
      (node (ref "C537") (pin "1") (pintype "passive"))
      (node (ref "C538") (pin "1") (pintype "passive"))
      (node (ref "C539") (pin "1") (pintype "passive"))
      (node (ref "DD34") (pin "101") (pinfunction "CONFIG1_101") (pintype "input"))
      (node (ref "DD34") (pin "110") (pinfunction "CONFIG10_110") (pintype "input"))
      (node (ref "DD34") (pin "119") (pinfunction "CONFIG5_119") (pintype "input"))
      (node (ref "DD34") (pin "120") (pinfunction "CONFIG4_120") (pintype "input"))
      (node (ref "DD34") (pin "121") (pinfunction "CONFIG3_121") (pintype "input"))
      (node (ref "DD34") (pin "122") (pinfunction "CONFIG0_122") (pintype "input"))
      (node (ref "DD34") (pin "129") (pinfunction "EPAD_129") (pintype "power_in"))
      (node (ref "DD34") (pin "43") (pinfunction "SDET_43") (pintype "input"))
      (node (ref "DD34") (pin "64") (pinfunction "CONFIG7_64") (pintype "input"))
      (node (ref "DD34") (pin "69") (pinfunction "CONFIG6_69") (pintype "input"))
      (node (ref "DD34") (pin "95") (pinfunction "CONFIG2_95") (pintype "input"))
      (node (ref "R589") (pin "2") (pintype "passive"))
      (node (ref "R594") (pin "1") (pintype "passive"))
      (node (ref "R596") (pin "1") (pintype "passive"))
      (node (ref "R599") (pin "1") (pintype "passive"))
    )
    (net (code "80") (name "Net-(DD34-RSET)") (class "Default")
      (node (ref "DD34") (pin "125") (pinfunction "RSET_125") (pintype "input"))
      (node (ref "R599") (pin "2") (pintype "passive"))
    )
    (net (code "81") (name "Net-(DD34-RX_CLK)") (class "Default")
      (node (ref "DD34") (pin "87") (pinfunction "RX_CLK_87") (pintype "output"))
      (node (ref "R592") (pin "1") (pintype "passive"))
    )
    (net (code "82") (name "Net-(DD34-SEL_RMII)") (class "Default")
      (node (ref "DD34") (pin "63") (pinfunction "SEL_RMII_63") (pintype "input"))
      (node (ref "R594") (pin "2") (pintype "passive"))
    )
    (net (code "83") (name "Net-(DD34-SMII_MODE0)") (class "Default")
      (node (ref "DD34") (pin "100") (pinfunction "SMII_MODE0_100") (pintype "input"))
      (node (ref "R588") (pin "1") (pintype "passive"))
    )
    (net (code "84") (name "Net-(DD34-SMII_MODE1)") (class "Default")
      (node (ref "DD34") (pin "99") (pinfunction "SMII_MODE1_99") (pintype "input"))
      (node (ref "R589") (pin "1") (pintype "passive"))
    )
    (net (code "85") (name "Net-(DD34-TRST#)") (class "Default")
      (node (ref "DD34") (pin "118") (pinfunction "TRST#_118") (pintype "input"))
      (node (ref "R596") (pin "2") (pintype "passive"))
    )
    (net (code "86") (name "Net-(VT31-E)") (class "Default")
      (node (ref "C514") (pin "2") (pintype "passive"))
      (node (ref "L56") (pin "1") (pinfunction "1_1") (pintype "passive"))
      (node (ref "R597") (pin "2") (pintype "passive"))
      (node (ref "VT31") (pin "3") (pinfunction "E_3") (pintype "passive"))
    )
    (net (code "87") (name "unconnected-(DD34-NORMAL-Pad113)") (class "Default")
      (node (ref "DD34") (pin "113") (pinfunction "NORMAL_113") (pintype "passive+no_connect"))
    )
    (net (code "88") (name "unconnected-(DD34-P1_LED1-Pad97)") (class "Default")
      (node (ref "DD34") (pin "97") (pinfunction "P1_LED1_97") (pintype "output+no_connect"))
    )
    (net (code "89") (name "unconnected-(DD34-P2_LED1-Pad93)") (class "Default")
      (node (ref "DD34") (pin "93") (pinfunction "P2_LED1_93") (pintype "output+no_connect"))
    )
    (net (code "90") (name "unconnected-(DD34-P3_LED1-Pad55)") (class "Default")
      (node (ref "DD34") (pin "55") (pinfunction "P3_LED1_55") (pintype "output+no_connect"))
    )
    (net (code "91") (name "unconnected-(DD34-P4_LED1-Pad52)") (class "Default")
      (node (ref "DD34") (pin "52") (pinfunction "P4_LED1_52") (pintype "output+no_connect"))
    )
    (net (code "92") (name "unconnected-(DD34-P5_LED1-Pad48)") (class "Default")
      (node (ref "DD34") (pin "48") (pinfunction "P5_LED1_48") (pintype "output+no_connect"))
    )
    (net (code "93") (name "unconnected-(DD34-P6_LED1-Pad67)") (class "Default")
      (node (ref "DD34") (pin "67") (pinfunction "P6_LED1_67") (pintype "output+no_connect"))
    )
    (net (code "94") (name "unconnected-(DD34-P7_LED1-Pad45)") (class "Default")
      (node (ref "DD34") (pin "45") (pinfunction "P7_LED1_45") (pintype "output+no_connect"))
    )
    (net (code "95") (name "unconnected-(DD34-TCK-Pad116)") (class "Default")
      (node (ref "DD34") (pin "116") (pinfunction "TCK_116") (pintype "passive+no_connect"))
    )
    (net (code "96") (name "unconnected-(DD34-TDI-Pad115)") (class "Default")
      (node (ref "DD34") (pin "115") (pinfunction "TDI_115") (pintype "passive+no_connect"))
    )
    (net (code "97") (name "unconnected-(DD34-TDO-Pad114)") (class "Default")
      (node (ref "DD34") (pin "114") (pinfunction "TDO_114") (pintype "passive+no_connect"))
    )
    (net (code "98") (name "unconnected-(DD34-TMS-Pad117)") (class "Default")
      (node (ref "DD34") (pin "117") (pinfunction "TMS_117") (pintype "passive+no_connect"))
    )
  )
)
